# GPIO_EXPANDER_LED.net
KiCad netlist of a schematic drawn in Altium Designer
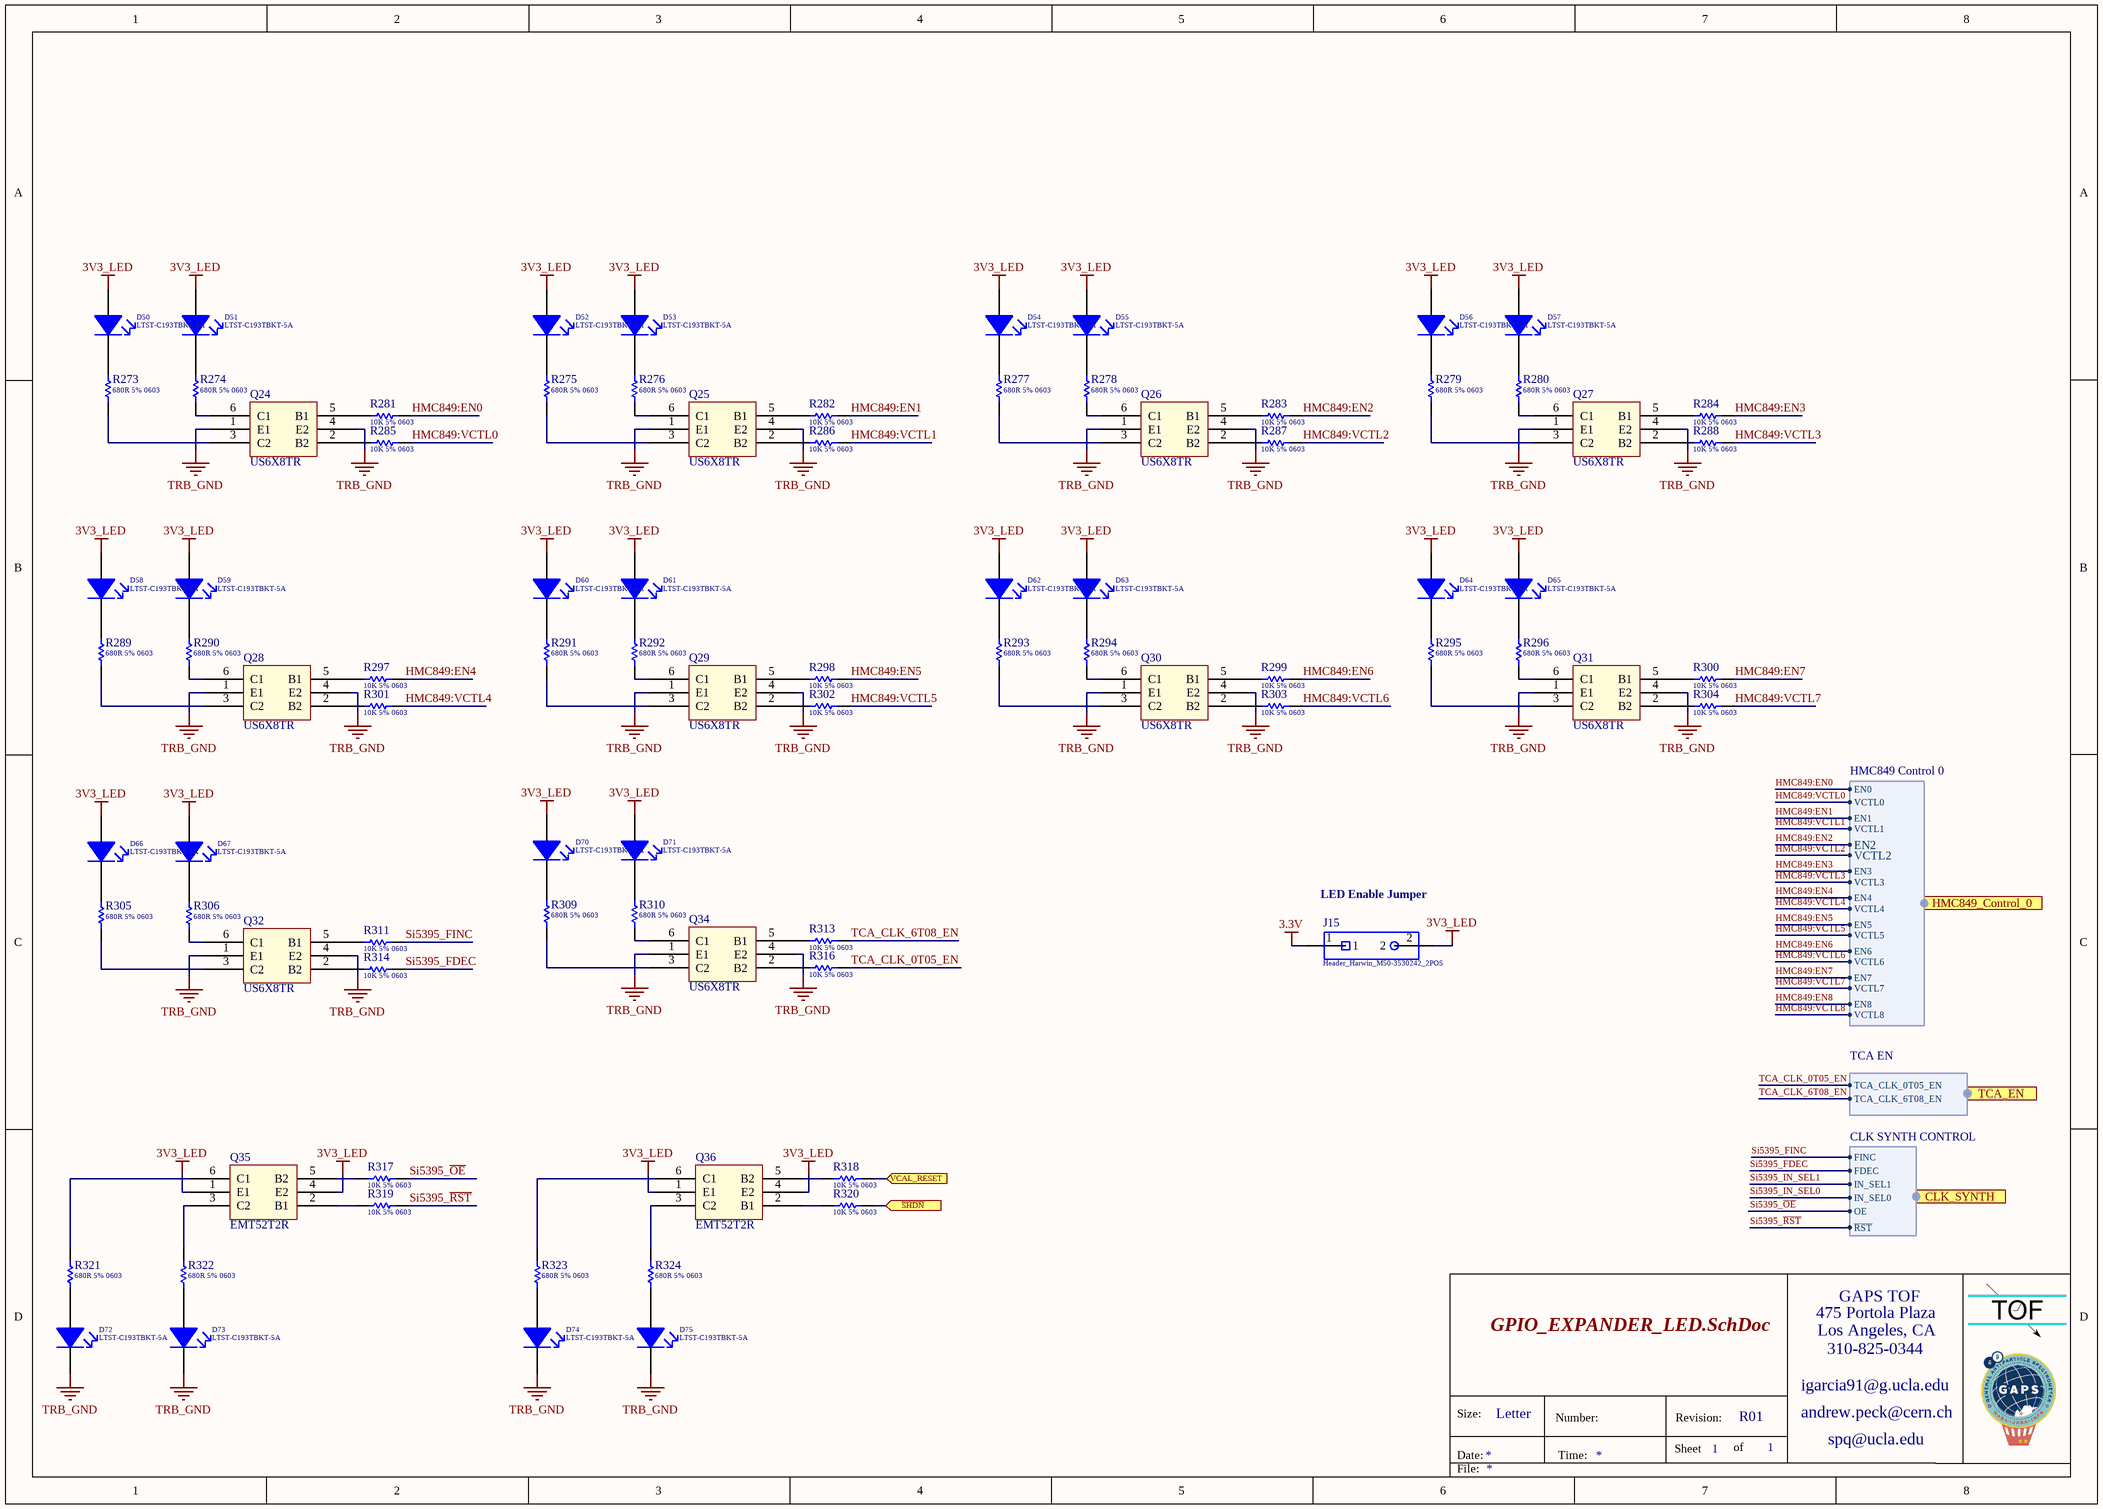
[diagram p0: GPIO_EXPANDER_LED.SchDoc]

(export (version "E")
  (design (tool "Eeschema 10.0.6"))
  (components
    (comp (ref "D50")
      (value "Led_Lite-On_LTST-C193TBKT-5A_Blue")
      (footprint "Led_Lite-On_LTST-C193TBKT-5A_Blue")
      (description "Standard LEDs - SMD Blue 470nm 28mcd 20mA")
      (fields (field (name "SERIES") "LTST-C193TBKT-5A"))
      (libsource (lib "Led_Lite-On_LTST-C193TBKT-5A_Blue") (part "Led_Lite-On_LTST-C193TBKT-5A_Blue"))
    )
    (comp (ref "D51")
      (value "Led_Lite-On_LTST-C193TBKT-5A_Blue")
      (footprint "Led_Lite-On_LTST-C193TBKT-5A_Blue")
      (description "Standard LEDs - SMD Blue 470nm 28mcd 20mA")
      (fields (field (name "SERIES") "LTST-C193TBKT-5A"))
      (libsource (lib "Led_Lite-On_LTST-C193TBKT-5A_Blue") (part "Led_Lite-On_LTST-C193TBKT-5A_Blue"))
    )
    (comp (ref "D52")
      (value "Led_Lite-On_LTST-C193TBKT-5A_Blue")
      (footprint "Led_Lite-On_LTST-C193TBKT-5A_Blue")
      (description "Standard LEDs - SMD Blue 470nm 28mcd 20mA")
      (fields (field (name "SERIES") "LTST-C193TBKT-5A"))
      (libsource (lib "Led_Lite-On_LTST-C193TBKT-5A_Blue") (part "Led_Lite-On_LTST-C193TBKT-5A_Blue"))
    )
    (comp (ref "D53")
      (value "Led_Lite-On_LTST-C193TBKT-5A_Blue")
      (footprint "Led_Lite-On_LTST-C193TBKT-5A_Blue")
      (description "Standard LEDs - SMD Blue 470nm 28mcd 20mA")
      (fields (field (name "SERIES") "LTST-C193TBKT-5A"))
      (libsource (lib "Led_Lite-On_LTST-C193TBKT-5A_Blue") (part "Led_Lite-On_LTST-C193TBKT-5A_Blue"))
    )
    (comp (ref "D54")
      (value "Led_Lite-On_LTST-C193TBKT-5A_Blue")
      (footprint "Led_Lite-On_LTST-C193TBKT-5A_Blue")
      (description "Standard LEDs - SMD Blue 470nm 28mcd 20mA")
      (fields (field (name "SERIES") "LTST-C193TBKT-5A"))
      (libsource (lib "Led_Lite-On_LTST-C193TBKT-5A_Blue") (part "Led_Lite-On_LTST-C193TBKT-5A_Blue"))
    )
    (comp (ref "D55")
      (value "Led_Lite-On_LTST-C193TBKT-5A_Blue")
      (footprint "Led_Lite-On_LTST-C193TBKT-5A_Blue")
      (description "Standard LEDs - SMD Blue 470nm 28mcd 20mA")
      (fields (field (name "SERIES") "LTST-C193TBKT-5A"))
      (libsource (lib "Led_Lite-On_LTST-C193TBKT-5A_Blue") (part "Led_Lite-On_LTST-C193TBKT-5A_Blue"))
    )
    (comp (ref "D56")
      (value "Led_Lite-On_LTST-C193TBKT-5A_Blue")
      (footprint "Led_Lite-On_LTST-C193TBKT-5A_Blue")
      (description "Standard LEDs - SMD Blue 470nm 28mcd 20mA")
      (fields (field (name "SERIES") "LTST-C193TBKT-5A"))
      (libsource (lib "Led_Lite-On_LTST-C193TBKT-5A_Blue") (part "Led_Lite-On_LTST-C193TBKT-5A_Blue"))
    )
    (comp (ref "D57")
      (value "Led_Lite-On_LTST-C193TBKT-5A_Blue")
      (footprint "Led_Lite-On_LTST-C193TBKT-5A_Blue")
      (description "Standard LEDs - SMD Blue 470nm 28mcd 20mA")
      (fields (field (name "SERIES") "LTST-C193TBKT-5A"))
      (libsource (lib "Led_Lite-On_LTST-C193TBKT-5A_Blue") (part "Led_Lite-On_LTST-C193TBKT-5A_Blue"))
    )
    (comp (ref "D58")
      (value "Led_Lite-On_LTST-C193TBKT-5A_Blue")
      (footprint "Led_Lite-On_LTST-C193TBKT-5A_Blue")
      (description "Standard LEDs - SMD Blue 470nm 28mcd 20mA")
      (fields (field (name "SERIES") "LTST-C193TBKT-5A"))
      (libsource (lib "Led_Lite-On_LTST-C193TBKT-5A_Blue") (part "Led_Lite-On_LTST-C193TBKT-5A_Blue"))
    )
    (comp (ref "D59")
      (value "Led_Lite-On_LTST-C193TBKT-5A_Blue")
      (footprint "Led_Lite-On_LTST-C193TBKT-5A_Blue")
      (description "Standard LEDs - SMD Blue 470nm 28mcd 20mA")
      (fields (field (name "SERIES") "LTST-C193TBKT-5A"))
      (libsource (lib "Led_Lite-On_LTST-C193TBKT-5A_Blue") (part "Led_Lite-On_LTST-C193TBKT-5A_Blue"))
    )
    (comp (ref "D60")
      (value "Led_Lite-On_LTST-C193TBKT-5A_Blue")
      (footprint "Led_Lite-On_LTST-C193TBKT-5A_Blue")
      (description "Standard LEDs - SMD Blue 470nm 28mcd 20mA")
      (fields (field (name "SERIES") "LTST-C193TBKT-5A"))
      (libsource (lib "Led_Lite-On_LTST-C193TBKT-5A_Blue") (part "Led_Lite-On_LTST-C193TBKT-5A_Blue"))
    )
    (comp (ref "D61")
      (value "Led_Lite-On_LTST-C193TBKT-5A_Blue")
      (footprint "Led_Lite-On_LTST-C193TBKT-5A_Blue")
      (description "Standard LEDs - SMD Blue 470nm 28mcd 20mA")
      (fields (field (name "SERIES") "LTST-C193TBKT-5A"))
      (libsource (lib "Led_Lite-On_LTST-C193TBKT-5A_Blue") (part "Led_Lite-On_LTST-C193TBKT-5A_Blue"))
    )
    (comp (ref "D62")
      (value "Led_Lite-On_LTST-C193TBKT-5A_Blue")
      (footprint "Led_Lite-On_LTST-C193TBKT-5A_Blue")
      (description "Standard LEDs - SMD Blue 470nm 28mcd 20mA")
      (fields (field (name "SERIES") "LTST-C193TBKT-5A"))
      (libsource (lib "Led_Lite-On_LTST-C193TBKT-5A_Blue") (part "Led_Lite-On_LTST-C193TBKT-5A_Blue"))
    )
    (comp (ref "D63")
      (value "Led_Lite-On_LTST-C193TBKT-5A_Blue")
      (footprint "Led_Lite-On_LTST-C193TBKT-5A_Blue")
      (description "Standard LEDs - SMD Blue 470nm 28mcd 20mA")
      (fields (field (name "SERIES") "LTST-C193TBKT-5A"))
      (libsource (lib "Led_Lite-On_LTST-C193TBKT-5A_Blue") (part "Led_Lite-On_LTST-C193TBKT-5A_Blue"))
    )
    (comp (ref "D64")
      (value "Led_Lite-On_LTST-C193TBKT-5A_Blue")
      (footprint "Led_Lite-On_LTST-C193TBKT-5A_Blue")
      (description "Standard LEDs - SMD Blue 470nm 28mcd 20mA")
      (fields (field (name "SERIES") "LTST-C193TBKT-5A"))
      (libsource (lib "Led_Lite-On_LTST-C193TBKT-5A_Blue") (part "Led_Lite-On_LTST-C193TBKT-5A_Blue"))
    )
    (comp (ref "D65")
      (value "Led_Lite-On_LTST-C193TBKT-5A_Blue")
      (footprint "Led_Lite-On_LTST-C193TBKT-5A_Blue")
      (description "Standard LEDs - SMD Blue 470nm 28mcd 20mA")
      (fields (field (name "SERIES") "LTST-C193TBKT-5A"))
      (libsource (lib "Led_Lite-On_LTST-C193TBKT-5A_Blue") (part "Led_Lite-On_LTST-C193TBKT-5A_Blue"))
    )
    (comp (ref "D66")
      (value "Led_Lite-On_LTST-C193TBKT-5A_Blue")
      (footprint "Led_Lite-On_LTST-C193TBKT-5A_Blue")
      (description "Standard LEDs - SMD Blue 470nm 28mcd 20mA")
      (fields (field (name "SERIES") "LTST-C193TBKT-5A"))
      (libsource (lib "Led_Lite-On_LTST-C193TBKT-5A_Blue") (part "Led_Lite-On_LTST-C193TBKT-5A_Blue"))
    )
    (comp (ref "D67")
      (value "Led_Lite-On_LTST-C193TBKT-5A_Blue")
      (footprint "Led_Lite-On_LTST-C193TBKT-5A_Blue")
      (description "Standard LEDs - SMD Blue 470nm 28mcd 20mA")
      (fields (field (name "SERIES") "LTST-C193TBKT-5A"))
      (libsource (lib "Led_Lite-On_LTST-C193TBKT-5A_Blue") (part "Led_Lite-On_LTST-C193TBKT-5A_Blue"))
    )
    (comp (ref "D70")
      (value "Led_Lite-On_LTST-C193TBKT-5A_Blue")
      (footprint "Led_Lite-On_LTST-C193TBKT-5A_Blue")
      (description "Standard LEDs - SMD Blue 470nm 28mcd 20mA")
      (fields (field (name "SERIES") "LTST-C193TBKT-5A"))
      (libsource (lib "Led_Lite-On_LTST-C193TBKT-5A_Blue") (part "Led_Lite-On_LTST-C193TBKT-5A_Blue"))
    )
    (comp (ref "D71")
      (value "Led_Lite-On_LTST-C193TBKT-5A_Blue")
      (footprint "Led_Lite-On_LTST-C193TBKT-5A_Blue")
      (description "Standard LEDs - SMD Blue 470nm 28mcd 20mA")
      (fields (field (name "SERIES") "LTST-C193TBKT-5A"))
      (libsource (lib "Led_Lite-On_LTST-C193TBKT-5A_Blue") (part "Led_Lite-On_LTST-C193TBKT-5A_Blue"))
    )
    (comp (ref "D72")
      (value "Led_Lite-On_LTST-C193TBKT-5A_Blue")
      (footprint "Led_Lite-On_LTST-C193TBKT-5A_Blue")
      (description "Standard LEDs - SMD Blue 470nm 28mcd 20mA")
      (fields (field (name "SERIES") "LTST-C193TBKT-5A"))
      (libsource (lib "Led_Lite-On_LTST-C193TBKT-5A_Blue") (part "Led_Lite-On_LTST-C193TBKT-5A_Blue"))
    )
    (comp (ref "D73")
      (value "Led_Lite-On_LTST-C193TBKT-5A_Blue")
      (footprint "Led_Lite-On_LTST-C193TBKT-5A_Blue")
      (description "Standard LEDs - SMD Blue 470nm 28mcd 20mA")
      (fields (field (name "SERIES") "LTST-C193TBKT-5A"))
      (libsource (lib "Led_Lite-On_LTST-C193TBKT-5A_Blue") (part "Led_Lite-On_LTST-C193TBKT-5A_Blue"))
    )
    (comp (ref "D74")
      (value "Led_Lite-On_LTST-C193TBKT-5A_Blue")
      (footprint "Led_Lite-On_LTST-C193TBKT-5A_Blue")
      (description "Standard LEDs - SMD Blue 470nm 28mcd 20mA")
      (fields (field (name "SERIES") "LTST-C193TBKT-5A"))
      (libsource (lib "Led_Lite-On_LTST-C193TBKT-5A_Blue") (part "Led_Lite-On_LTST-C193TBKT-5A_Blue"))
    )
    (comp (ref "D75")
      (value "Led_Lite-On_LTST-C193TBKT-5A_Blue")
      (footprint "Led_Lite-On_LTST-C193TBKT-5A_Blue")
      (description "Standard LEDs - SMD Blue 470nm 28mcd 20mA")
      (fields (field (name "SERIES") "LTST-C193TBKT-5A"))
      (libsource (lib "Led_Lite-On_LTST-C193TBKT-5A_Blue") (part "Led_Lite-On_LTST-C193TBKT-5A_Blue"))
    )
    (comp (ref "J15")
      (value "Header_Harwin_M50-3530242_2POS")
      (footprint "Header_Harwin_M50-3530242_2POS")
      (description "Headers & Wire Housings 2 WAY SIL VERT PC TAIL P/HDR")
      (libsource (lib "Header_Harwin_M50-3530242_2POS") (part "Header_Harwin_M50-3530242_2POS"))
    )
    (comp (ref "Q24")
      (value "BJT_ROHM_US6X8TR_1A_NPN")
      (footprint "BJT_ROHM_US6X8TR_1A_NPN")
      (description "Bipolar Transistors - BJT NPN+NPN 30VCEO 1A SOT-363T")
      (fields (field (name "SERIES") "US6X8TR"))
      (libsource (lib "BJT_ROHM_US6X8TR_1A_NPN") (part "BJT_ROHM_US6X8TR_1A_NPN"))
    )
    (comp (ref "Q25")
      (value "BJT_ROHM_US6X8TR_1A_NPN")
      (footprint "BJT_ROHM_US6X8TR_1A_NPN")
      (description "Bipolar Transistors - BJT NPN+NPN 30VCEO 1A SOT-363T")
      (fields (field (name "SERIES") "US6X8TR"))
      (libsource (lib "BJT_ROHM_US6X8TR_1A_NPN") (part "BJT_ROHM_US6X8TR_1A_NPN"))
    )
    (comp (ref "Q26")
      (value "BJT_ROHM_US6X8TR_1A_NPN")
      (footprint "BJT_ROHM_US6X8TR_1A_NPN")
      (description "Bipolar Transistors - BJT NPN+NPN 30VCEO 1A SOT-363T")
      (fields (field (name "SERIES") "US6X8TR"))
      (libsource (lib "BJT_ROHM_US6X8TR_1A_NPN") (part "BJT_ROHM_US6X8TR_1A_NPN"))
    )
    (comp (ref "Q27")
      (value "BJT_ROHM_US6X8TR_1A_NPN")
      (footprint "BJT_ROHM_US6X8TR_1A_NPN")
      (description "Bipolar Transistors - BJT NPN+NPN 30VCEO 1A SOT-363T")
      (fields (field (name "SERIES") "US6X8TR"))
      (libsource (lib "BJT_ROHM_US6X8TR_1A_NPN") (part "BJT_ROHM_US6X8TR_1A_NPN"))
    )
    (comp (ref "Q28")
      (value "BJT_ROHM_US6X8TR_1A_NPN")
      (footprint "BJT_ROHM_US6X8TR_1A_NPN")
      (description "Bipolar Transistors - BJT NPN+NPN 30VCEO 1A SOT-363T")
      (fields (field (name "SERIES") "US6X8TR"))
      (libsource (lib "BJT_ROHM_US6X8TR_1A_NPN") (part "BJT_ROHM_US6X8TR_1A_NPN"))
    )
    (comp (ref "Q29")
      (value "BJT_ROHM_US6X8TR_1A_NPN")
      (footprint "BJT_ROHM_US6X8TR_1A_NPN")
      (description "Bipolar Transistors - BJT NPN+NPN 30VCEO 1A SOT-363T")
      (fields (field (name "SERIES") "US6X8TR"))
      (libsource (lib "BJT_ROHM_US6X8TR_1A_NPN") (part "BJT_ROHM_US6X8TR_1A_NPN"))
    )
    (comp (ref "Q30")
      (value "BJT_ROHM_US6X8TR_1A_NPN")
      (footprint "BJT_ROHM_US6X8TR_1A_NPN")
      (description "Bipolar Transistors - BJT NPN+NPN 30VCEO 1A SOT-363T")
      (fields (field (name "SERIES") "US6X8TR"))
      (libsource (lib "BJT_ROHM_US6X8TR_1A_NPN") (part "BJT_ROHM_US6X8TR_1A_NPN"))
    )
    (comp (ref "Q31")
      (value "BJT_ROHM_US6X8TR_1A_NPN")
      (footprint "BJT_ROHM_US6X8TR_1A_NPN")
      (description "Bipolar Transistors - BJT NPN+NPN 30VCEO 1A SOT-363T")
      (fields (field (name "SERIES") "US6X8TR"))
      (libsource (lib "BJT_ROHM_US6X8TR_1A_NPN") (part "BJT_ROHM_US6X8TR_1A_NPN"))
    )
    (comp (ref "Q32")
      (value "BJT_ROHM_US6X8TR_1A_NPN")
      (footprint "BJT_ROHM_US6X8TR_1A_NPN")
      (description "Bipolar Transistors - BJT NPN+NPN 30VCEO 1A SOT-363T")
      (fields (field (name "SERIES") "US6X8TR"))
      (libsource (lib "BJT_ROHM_US6X8TR_1A_NPN") (part "BJT_ROHM_US6X8TR_1A_NPN"))
    )
    (comp (ref "Q34")
      (value "BJT_ROHM_US6X8TR_1A_NPN")
      (footprint "BJT_ROHM_US6X8TR_1A_NPN")
      (description "Bipolar Transistors - BJT NPN+NPN 30VCEO 1A SOT-363T")
      (fields (field (name "SERIES") "US6X8TR"))
      (libsource (lib "BJT_ROHM_US6X8TR_1A_NPN") (part "BJT_ROHM_US6X8TR_1A_NPN"))
    )
    (comp (ref "Q35")
      (value "BJT_ROHM_EMT52T2R_100mA_PNP")
      (footprint "BJT_ROHM_EMT52T2R_100mA_PNP")
      (description "Bipolar Transistors - BJT Bipolar Transistor SOT-563 SC-107C EMT6")
      (fields (field (name "SERIES") "EMT52T2R"))
      (libsource (lib "BJT_ROHM_EMT52T2R_100mA_PNP") (part "BJT_ROHM_EMT52T2R_100mA_PNP"))
    )
    (comp (ref "Q36")
      (value "BJT_ROHM_EMT52T2R_100mA_PNP")
      (footprint "BJT_ROHM_EMT52T2R_100mA_PNP")
      (description "Bipolar Transistors - BJT Bipolar Transistor SOT-563 SC-107C EMT6")
      (fields (field (name "SERIES") "EMT52T2R"))
      (libsource (lib "BJT_ROHM_EMT52T2R_100mA_PNP") (part "BJT_ROHM_EMT52T2R_100mA_PNP"))
    )
    (comp (ref "R273")
      (value "680R 5% 0603")
      (footprint "RESC0603(1608)_L")
      (description "680R 0.1W 5% 0603 (1608 Metric)  SMD")
      (fields (field (name "TOLERANCE") "5 %") (field (name "POWER") "0.1 W"))
      (libsource (lib "Altium Content Vault") (part "RES"))
    )
    (comp (ref "R274")
      (value "680R 5% 0603")
      (footprint "RESC0603(1608)_L")
      (description "680R 0.1W 5% 0603 (1608 Metric)  SMD")
      (fields (field (name "TOLERANCE") "5 %") (field (name "POWER") "0.1 W"))
      (libsource (lib "Altium Content Vault") (part "RES"))
    )
    (comp (ref "R275")
      (value "680R 5% 0603")
      (footprint "RESC0603(1608)_L")
      (description "680R 0.1W 5% 0603 (1608 Metric)  SMD")
      (fields (field (name "TOLERANCE") "5 %") (field (name "POWER") "0.1 W"))
      (libsource (lib "Altium Content Vault") (part "RES"))
    )
    (comp (ref "R276")
      (value "680R 5% 0603")
      (footprint "RESC0603(1608)_L")
      (description "680R 0.1W 5% 0603 (1608 Metric)  SMD")
      (fields (field (name "TOLERANCE") "5 %") (field (name "POWER") "0.1 W"))
      (libsource (lib "Altium Content Vault") (part "RES"))
    )
    (comp (ref "R277")
      (value "680R 5% 0603")
      (footprint "RESC0603(1608)_L")
      (description "680R 0.1W 5% 0603 (1608 Metric)  SMD")
      (fields (field (name "TOLERANCE") "5 %") (field (name "POWER") "0.1 W"))
      (libsource (lib "Altium Content Vault") (part "RES"))
    )
    (comp (ref "R278")
      (value "680R 5% 0603")
      (footprint "RESC0603(1608)_L")
      (description "680R 0.1W 5% 0603 (1608 Metric)  SMD")
      (fields (field (name "TOLERANCE") "5 %") (field (name "POWER") "0.1 W"))
      (libsource (lib "Altium Content Vault") (part "RES"))
    )
    (comp (ref "R279")
      (value "680R 5% 0603")
      (footprint "RESC0603(1608)_L")
      (description "680R 0.1W 5% 0603 (1608 Metric)  SMD")
      (fields (field (name "TOLERANCE") "5 %") (field (name "POWER") "0.1 W"))
      (libsource (lib "Altium Content Vault") (part "RES"))
    )
    (comp (ref "R280")
      (value "680R 5% 0603")
      (footprint "RESC0603(1608)_L")
      (description "680R 0.1W 5% 0603 (1608 Metric)  SMD")
      (fields (field (name "TOLERANCE") "5 %") (field (name "POWER") "0.1 W"))
      (libsource (lib "Altium Content Vault") (part "RES"))
    )
    (comp (ref "R281")
      (value "10K 5% 0603")
      (footprint "RESC0603(1608)_L")
      (description "10K 0.1W 5% 0603 (1608 Metric)  SMD")
      (fields (field (name "TOLERANCE") "5 %") (field (name "POWER") "0.1 W"))
      (libsource (lib "Altium Content Vault") (part "RES"))
    )
    (comp (ref "R282")
      (value "10K 5% 0603")
      (footprint "RESC0603(1608)_L")
      (description "10K 0.1W 5% 0603 (1608 Metric)  SMD")
      (fields (field (name "TOLERANCE") "5 %") (field (name "POWER") "0.1 W"))
      (libsource (lib "Altium Content Vault") (part "RES"))
    )
    (comp (ref "R283")
      (value "10K 5% 0603")
      (footprint "RESC0603(1608)_L")
      (description "10K 0.1W 5% 0603 (1608 Metric)  SMD")
      (fields (field (name "TOLERANCE") "5 %") (field (name "POWER") "0.1 W"))
      (libsource (lib "Altium Content Vault") (part "RES"))
    )
    (comp (ref "R284")
      (value "10K 5% 0603")
      (footprint "RESC0603(1608)_L")
      (description "10K 0.1W 5% 0603 (1608 Metric)  SMD")
      (fields (field (name "TOLERANCE") "5 %") (field (name "POWER") "0.1 W"))
      (libsource (lib "Altium Content Vault") (part "RES"))
    )
    (comp (ref "R285")
      (value "10K 5% 0603")
      (footprint "RESC0603(1608)_L")
      (description "10K 0.1W 5% 0603 (1608 Metric)  SMD")
      (fields (field (name "TOLERANCE") "5 %") (field (name "POWER") "0.1 W"))
      (libsource (lib "Altium Content Vault") (part "RES"))
    )
    (comp (ref "R286")
      (value "10K 5% 0603")
      (footprint "RESC0603(1608)_L")
      (description "10K 0.1W 5% 0603 (1608 Metric)  SMD")
      (fields (field (name "TOLERANCE") "5 %") (field (name "POWER") "0.1 W"))
      (libsource (lib "Altium Content Vault") (part "RES"))
    )
    (comp (ref "R287")
      (value "10K 5% 0603")
      (footprint "RESC0603(1608)_L")
      (description "10K 0.1W 5% 0603 (1608 Metric)  SMD")
      (fields (field (name "TOLERANCE") "5 %") (field (name "POWER") "0.1 W"))
      (libsource (lib "Altium Content Vault") (part "RES"))
    )
    (comp (ref "R288")
      (value "10K 5% 0603")
      (footprint "RESC0603(1608)_L")
      (description "10K 0.1W 5% 0603 (1608 Metric)  SMD")
      (fields (field (name "TOLERANCE") "5 %") (field (name "POWER") "0.1 W"))
      (libsource (lib "Altium Content Vault") (part "RES"))
    )
    (comp (ref "R289")
      (value "680R 5% 0603")
      (footprint "RESC0603(1608)_L")
      (description "680R 0.1W 5% 0603 (1608 Metric)  SMD")
      (fields (field (name "TOLERANCE") "5 %") (field (name "POWER") "0.1 W"))
      (libsource (lib "Altium Content Vault") (part "RES"))
    )
    (comp (ref "R290")
      (value "680R 5% 0603")
      (footprint "RESC0603(1608)_L")
      (description "680R 0.1W 5% 0603 (1608 Metric)  SMD")
      (fields (field (name "TOLERANCE") "5 %") (field (name "POWER") "0.1 W"))
      (libsource (lib "Altium Content Vault") (part "RES"))
    )
    (comp (ref "R291")
      (value "680R 5% 0603")
      (footprint "RESC0603(1608)_L")
      (description "680R 0.1W 5% 0603 (1608 Metric)  SMD")
      (fields (field (name "TOLERANCE") "5 %") (field (name "POWER") "0.1 W"))
      (libsource (lib "Altium Content Vault") (part "RES"))
    )
    (comp (ref "R292")
      (value "680R 5% 0603")
      (footprint "RESC0603(1608)_L")
      (description "680R 0.1W 5% 0603 (1608 Metric)  SMD")
      (fields (field (name "TOLERANCE") "5 %") (field (name "POWER") "0.1 W"))
      (libsource (lib "Altium Content Vault") (part "RES"))
    )
    (comp (ref "R293")
      (value "680R 5% 0603")
      (footprint "RESC0603(1608)_L")
      (description "680R 0.1W 5% 0603 (1608 Metric)  SMD")
      (fields (field (name "TOLERANCE") "5 %") (field (name "POWER") "0.1 W"))
      (libsource (lib "Altium Content Vault") (part "RES"))
    )
    (comp (ref "R294")
      (value "680R 5% 0603")
      (footprint "RESC0603(1608)_L")
      (description "680R 0.1W 5% 0603 (1608 Metric)  SMD")
      (fields (field (name "TOLERANCE") "5 %") (field (name "POWER") "0.1 W"))
      (libsource (lib "Altium Content Vault") (part "RES"))
    )
    (comp (ref "R295")
      (value "680R 5% 0603")
      (footprint "RESC0603(1608)_L")
      (description "680R 0.1W 5% 0603 (1608 Metric)  SMD")
      (fields (field (name "TOLERANCE") "5 %") (field (name "POWER") "0.1 W"))
      (libsource (lib "Altium Content Vault") (part "RES"))
    )
    (comp (ref "R296")
      (value "680R 5% 0603")
      (footprint "RESC0603(1608)_L")
      (description "680R 0.1W 5% 0603 (1608 Metric)  SMD")
      (fields (field (name "TOLERANCE") "5 %") (field (name "POWER") "0.1 W"))
      (libsource (lib "Altium Content Vault") (part "RES"))
    )
    (comp (ref "R297")
      (value "10K 5% 0603")
      (footprint "RESC0603(1608)_L")
      (description "10K 0.1W 5% 0603 (1608 Metric)  SMD")
      (fields (field (name "TOLERANCE") "5 %") (field (name "POWER") "0.1 W"))
      (libsource (lib "Altium Content Vault") (part "RES"))
    )
    (comp (ref "R298")
      (value "10K 5% 0603")
      (footprint "RESC0603(1608)_L")
      (description "10K 0.1W 5% 0603 (1608 Metric)  SMD")
      (fields (field (name "TOLERANCE") "5 %") (field (name "POWER") "0.1 W"))
      (libsource (lib "Altium Content Vault") (part "RES"))
    )
    (comp (ref "R299")
      (value "10K 5% 0603")
      (footprint "RESC0603(1608)_L")
      (description "10K 0.1W 5% 0603 (1608 Metric)  SMD")
      (fields (field (name "TOLERANCE") "5 %") (field (name "POWER") "0.1 W"))
      (libsource (lib "Altium Content Vault") (part "RES"))
    )
    (comp (ref "R300")
      (value "10K 5% 0603")
      (footprint "RESC0603(1608)_L")
      (description "10K 0.1W 5% 0603 (1608 Metric)  SMD")
      (fields (field (name "TOLERANCE") "5 %") (field (name "POWER") "0.1 W"))
      (libsource (lib "Altium Content Vault") (part "RES"))
    )
    (comp (ref "R301")
      (value "10K 5% 0603")
      (footprint "RESC0603(1608)_L")
      (description "10K 0.1W 5% 0603 (1608 Metric)  SMD")
      (fields (field (name "TOLERANCE") "5 %") (field (name "POWER") "0.1 W"))
      (libsource (lib "Altium Content Vault") (part "RES"))
    )
    (comp (ref "R302")
      (value "10K 5% 0603")
      (footprint "RESC0603(1608)_L")
      (description "10K 0.1W 5% 0603 (1608 Metric)  SMD")
      (fields (field (name "TOLERANCE") "5 %") (field (name "POWER") "0.1 W"))
      (libsource (lib "Altium Content Vault") (part "RES"))
    )
    (comp (ref "R303")
      (value "10K 5% 0603")
      (footprint "RESC0603(1608)_L")
      (description "10K 0.1W 5% 0603 (1608 Metric)  SMD")
      (fields (field (name "TOLERANCE") "5 %") (field (name "POWER") "0.1 W"))
      (libsource (lib "Altium Content Vault") (part "RES"))
    )
    (comp (ref "R304")
      (value "10K 5% 0603")
      (footprint "RESC0603(1608)_L")
      (description "10K 0.1W 5% 0603 (1608 Metric)  SMD")
      (fields (field (name "TOLERANCE") "5 %") (field (name "POWER") "0.1 W"))
      (libsource (lib "Altium Content Vault") (part "RES"))
    )
    (comp (ref "R305")
      (value "680R 5% 0603")
      (footprint "RESC0603(1608)_L")
      (description "680R 0.1W 5% 0603 (1608 Metric)  SMD")
      (fields (field (name "TOLERANCE") "5 %") (field (name "POWER") "0.1 W"))
      (libsource (lib "Altium Content Vault") (part "RES"))
    )
    (comp (ref "R306")
      (value "680R 5% 0603")
      (footprint "RESC0603(1608)_L")
      (description "680R 0.1W 5% 0603 (1608 Metric)  SMD")
      (fields (field (name "TOLERANCE") "5 %") (field (name "POWER") "0.1 W"))
      (libsource (lib "Altium Content Vault") (part "RES"))
    )
    (comp (ref "R309")
      (value "680R 5% 0603")
      (footprint "RESC0603(1608)_L")
      (description "680R 0.1W 5% 0603 (1608 Metric)  SMD")
      (fields (field (name "TOLERANCE") "5 %") (field (name "POWER") "0.1 W"))
      (libsource (lib "Altium Content Vault") (part "RES"))
    )
    (comp (ref "R310")
      (value "680R 5% 0603")
      (footprint "RESC0603(1608)_L")
      (description "680R 0.1W 5% 0603 (1608 Metric)  SMD")
      (fields (field (name "TOLERANCE") "5 %") (field (name "POWER") "0.1 W"))
      (libsource (lib "Altium Content Vault") (part "RES"))
    )
    (comp (ref "R311")
      (value "10K 5% 0603")
      (footprint "RESC0603(1608)_L")
      (description "10K 0.1W 5% 0603 (1608 Metric)  SMD")
      (fields (field (name "TOLERANCE") "5 %") (field (name "POWER") "0.1 W"))
      (libsource (lib "Altium Content Vault") (part "RES"))
    )
    (comp (ref "R313")
      (value "10K 5% 0603")
      (footprint "RESC0603(1608)_L")
      (description "10K 0.1W 5% 0603 (1608 Metric)  SMD")
      (fields (field (name "TOLERANCE") "5 %") (field (name "POWER") "0.1 W"))
      (libsource (lib "Altium Content Vault") (part "RES"))
    )
    (comp (ref "R314")
      (value "10K 5% 0603")
      (footprint "RESC0603(1608)_L")
      (description "10K 0.1W 5% 0603 (1608 Metric)  SMD")
      (fields (field (name "TOLERANCE") "5 %") (field (name "POWER") "0.1 W"))
      (libsource (lib "Altium Content Vault") (part "RES"))
    )
    (comp (ref "R316")
      (value "10K 5% 0603")
      (footprint "RESC0603(1608)_L")
      (description "10K 0.1W 5% 0603 (1608 Metric)  SMD")
      (fields (field (name "TOLERANCE") "5 %") (field (name "POWER") "0.1 W"))
      (libsource (lib "Altium Content Vault") (part "RES"))
    )
    (comp (ref "R317")
      (value "10K 5% 0603")
      (footprint "RESC0603(1608)_L")
      (description "10K 0.1W 5% 0603 (1608 Metric)  SMD")
      (fields (field (name "TOLERANCE") "5 %") (field (name "POWER") "0.1 W"))
      (libsource (lib "Altium Content Vault") (part "RES"))
    )
    (comp (ref "R318")
      (value "10K 5% 0603")
      (footprint "RESC0603(1608)_L")
      (description "10K 0.1W 5% 0603 (1608 Metric)  SMD")
      (fields (field (name "TOLERANCE") "5 %") (field (name "POWER") "0.1 W"))
      (libsource (lib "Altium Content Vault") (part "RES"))
    )
    (comp (ref "R319")
      (value "10K 5% 0603")
      (footprint "RESC0603(1608)_L")
      (description "10K 0.1W 5% 0603 (1608 Metric)  SMD")
      (fields (field (name "TOLERANCE") "5 %") (field (name "POWER") "0.1 W"))
      (libsource (lib "Altium Content Vault") (part "RES"))
    )
    (comp (ref "R320")
      (value "10K 5% 0603")
      (footprint "RESC0603(1608)_L")
      (description "10K 0.1W 5% 0603 (1608 Metric)  SMD")
      (fields (field (name "TOLERANCE") "5 %") (field (name "POWER") "0.1 W"))
      (libsource (lib "Altium Content Vault") (part "RES"))
    )
    (comp (ref "R321")
      (value "680R 5% 0603")
      (footprint "RESC0603(1608)_L")
      (description "680R 0.1W 5% 0603 (1608 Metric)  SMD")
      (fields (field (name "TOLERANCE") "5 %") (field (name "POWER") "0.1 W"))
      (libsource (lib "Altium Content Vault") (part "RES"))
    )
    (comp (ref "R322")
      (value "680R 5% 0603")
      (footprint "RESC0603(1608)_L")
      (description "680R 0.1W 5% 0603 (1608 Metric)  SMD")
      (fields (field (name "TOLERANCE") "5 %") (field (name "POWER") "0.1 W"))
      (libsource (lib "Altium Content Vault") (part "RES"))
    )
    (comp (ref "R323")
      (value "680R 5% 0603")
      (footprint "RESC0603(1608)_L")
      (description "680R 0.1W 5% 0603 (1608 Metric)  SMD")
      (fields (field (name "TOLERANCE") "5 %") (field (name "POWER") "0.1 W"))
      (libsource (lib "Altium Content Vault") (part "RES"))
    )
    (comp (ref "R324")
      (value "680R 5% 0603")
      (footprint "RESC0603(1608)_L")
      (description "680R 0.1W 5% 0603 (1608 Metric)  SMD")
      (fields (field (name "TOLERANCE") "5 %") (field (name "POWER") "0.1 W"))
      (libsource (lib "Altium Content Vault") (part "RES"))
    )
  )
  (nets
    (net (code "9") (name "/HMC849:EN0") (class "Default")
      (node (ref "R281") (pin "2") (pinfunction "2_2") (pintype "passive"))
    )
    (net (code "10") (name "/HMC849:EN1") (class "Default")
      (node (ref "R282") (pin "2") (pinfunction "2_2") (pintype "passive"))
    )
    (net (code "11") (name "/HMC849:EN2") (class "Default")
      (node (ref "R283") (pin "2") (pinfunction "2_2") (pintype "passive"))
    )
    (net (code "12") (name "/HMC849:EN3") (class "Default")
      (node (ref "R284") (pin "2") (pinfunction "2_2") (pintype "passive"))
    )
    (net (code "13") (name "/HMC849:EN4") (class "Default")
      (node (ref "R297") (pin "2") (pinfunction "2_2") (pintype "passive"))
    )
    (net (code "14") (name "/HMC849:EN5") (class "Default")
      (node (ref "R298") (pin "2") (pinfunction "2_2") (pintype "passive"))
    )
    (net (code "15") (name "/HMC849:EN6") (class "Default")
      (node (ref "R299") (pin "2") (pinfunction "2_2") (pintype "passive"))
    )
    (net (code "16") (name "/HMC849:EN7") (class "Default")
      (node (ref "R300") (pin "2") (pinfunction "2_2") (pintype "passive"))
    )
    (net (code "18") (name "/HMC849:VCTL0") (class "Default")
      (node (ref "R285") (pin "1") (pinfunction "1_1") (pintype "passive"))
    )
    (net (code "19") (name "/HMC849:VCTL1") (class "Default")
      (node (ref "R286") (pin "1") (pinfunction "1_1") (pintype "passive"))
    )
    (net (code "20") (name "/HMC849:VCTL2") (class "Default")
      (node (ref "R287") (pin "1") (pinfunction "1_1") (pintype "passive"))
    )
    (net (code "21") (name "/HMC849:VCTL3") (class "Default")
      (node (ref "R288") (pin "1") (pinfunction "1_1") (pintype "passive"))
    )
    (net (code "22") (name "/HMC849:VCTL4") (class "Default")
      (node (ref "R301") (pin "1") (pinfunction "1_1") (pintype "passive"))
    )
    (net (code "23") (name "/HMC849:VCTL5") (class "Default")
      (node (ref "R302") (pin "1") (pinfunction "1_1") (pintype "passive"))
    )
    (net (code "24") (name "/HMC849:VCTL6") (class "Default")
      (node (ref "R303") (pin "1") (pinfunction "1_1") (pintype "passive"))
    )
    (net (code "25") (name "/HMC849:VCTL7") (class "Default")
      (node (ref "R304") (pin "1") (pinfunction "1_1") (pintype "passive"))
    )
    (net (code "27") (name "/Si5395_FDEC") (class "Default")
      (node (ref "R314") (pin "1") (pinfunction "1_1") (pintype "passive"))
    )
    (net (code "28") (name "/Si5395_FINC") (class "Default")
      (node (ref "R311") (pin "2") (pinfunction "2_2") (pintype "passive"))
    )
    (net (code "31") (name "/Si5395_~{OE}") (class "Default")
      (node (ref "R317") (pin "1") (pinfunction "1_1") (pintype "passive"))
    )
    (net (code "32") (name "/Si5395_~{RST}") (class "Default")
      (node (ref "R319") (pin "2") (pinfunction "2_2") (pintype "passive"))
    )
    (net (code "33") (name "/TCA_CLK_0T05_EN") (class "Default")
      (node (ref "R316") (pin "1") (pinfunction "1_1") (pintype "passive"))
    )
    (net (code "34") (name "/TCA_CLK_6T08_EN") (class "Default")
      (node (ref "R313") (pin "2") (pinfunction "2_2") (pintype "passive"))
    )
    (net (code "35") (name "/VCAL_RESET") (class "Default")
      (node (ref "R318") (pin "1") (pinfunction "1_1") (pintype "passive"))
    )
    (net (code "39") (name "/~{SHDN}") (class "Default")
      (node (ref "R320") (pin "2") (pinfunction "2_2") (pintype "passive"))
    )
    (net (code "40") (name "3.3V") (class "Default")
      (node (ref "J15") (pin "1") (pinfunction "1_1") (pintype "passive"))
    )
    (net (code "41") (name "3V3_LED") (class "Default")
      (node (ref "D50") (pin "2") (pinfunction "A_2") (pintype "passive"))
      (node (ref "D51") (pin "2") (pinfunction "A_2") (pintype "passive"))
      (node (ref "D52") (pin "2") (pinfunction "A_2") (pintype "passive"))
      (node (ref "D53") (pin "2") (pinfunction "A_2") (pintype "passive"))
      (node (ref "D54") (pin "2") (pinfunction "A_2") (pintype "passive"))
      (node (ref "D55") (pin "2") (pinfunction "A_2") (pintype "passive"))
      (node (ref "D56") (pin "2") (pinfunction "A_2") (pintype "passive"))
      (node (ref "D57") (pin "2") (pinfunction "A_2") (pintype "passive"))
      (node (ref "D58") (pin "2") (pinfunction "A_2") (pintype "passive"))
      (node (ref "D59") (pin "2") (pinfunction "A_2") (pintype "passive"))
      (node (ref "D60") (pin "2") (pinfunction "A_2") (pintype "passive"))
      (node (ref "D61") (pin "2") (pinfunction "A_2") (pintype "passive"))
      (node (ref "D62") (pin "2") (pinfunction "A_2") (pintype "passive"))
      (node (ref "D63") (pin "2") (pinfunction "A_2") (pintype "passive"))
      (node (ref "D64") (pin "2") (pinfunction "A_2") (pintype "passive"))
      (node (ref "D65") (pin "2") (pinfunction "A_2") (pintype "passive"))
      (node (ref "D66") (pin "2") (pinfunction "A_2") (pintype "passive"))
      (node (ref "D67") (pin "2") (pinfunction "A_2") (pintype "passive"))
      (node (ref "D70") (pin "2") (pinfunction "A_2") (pintype "passive"))
      (node (ref "D71") (pin "2") (pinfunction "A_2") (pintype "passive"))
      (node (ref "J15") (pin "2") (pinfunction "2_2") (pintype "passive"))
      (node (ref "Q35") (pin "1") (pinfunction "E1_1") (pintype "passive"))
      (node (ref "Q35") (pin "4") (pinfunction "E2_4") (pintype "passive"))
      (node (ref "Q36") (pin "1") (pinfunction "E1_1") (pintype "passive"))
      (node (ref "Q36") (pin "4") (pinfunction "E2_4") (pintype "passive"))
    )
    (net (code "42") (name "Net-(D50-K)") (class "Default")
      (node (ref "D50") (pin "1") (pinfunction "K_1") (pintype "passive"))
      (node (ref "R273") (pin "2") (pinfunction "2_2") (pintype "passive"))
    )
    (net (code "43") (name "Net-(D51-K)") (class "Default")
      (node (ref "D51") (pin "1") (pinfunction "K_1") (pintype "passive"))
      (node (ref "R274") (pin "2") (pinfunction "2_2") (pintype "passive"))
    )
    (net (code "44") (name "Net-(D52-K)") (class "Default")
      (node (ref "D52") (pin "1") (pinfunction "K_1") (pintype "passive"))
      (node (ref "R275") (pin "2") (pinfunction "2_2") (pintype "passive"))
    )
    (net (code "45") (name "Net-(D53-K)") (class "Default")
      (node (ref "D53") (pin "1") (pinfunction "K_1") (pintype "passive"))
      (node (ref "R276") (pin "2") (pinfunction "2_2") (pintype "passive"))
    )
    (net (code "46") (name "Net-(D54-K)") (class "Default")
      (node (ref "D54") (pin "1") (pinfunction "K_1") (pintype "passive"))
      (node (ref "R277") (pin "2") (pinfunction "2_2") (pintype "passive"))
    )
    (net (code "47") (name "Net-(D55-K)") (class "Default")
      (node (ref "D55") (pin "1") (pinfunction "K_1") (pintype "passive"))
      (node (ref "R278") (pin "2") (pinfunction "2_2") (pintype "passive"))
    )
    (net (code "48") (name "Net-(D56-K)") (class "Default")
      (node (ref "D56") (pin "1") (pinfunction "K_1") (pintype "passive"))
      (node (ref "R279") (pin "2") (pinfunction "2_2") (pintype "passive"))
    )
    (net (code "49") (name "Net-(D57-K)") (class "Default")
      (node (ref "D57") (pin "1") (pinfunction "K_1") (pintype "passive"))
      (node (ref "R280") (pin "2") (pinfunction "2_2") (pintype "passive"))
    )
    (net (code "50") (name "Net-(D58-K)") (class "Default")
      (node (ref "D58") (pin "1") (pinfunction "K_1") (pintype "passive"))
      (node (ref "R289") (pin "2") (pinfunction "2_2") (pintype "passive"))
    )
    (net (code "51") (name "Net-(D59-K)") (class "Default")
      (node (ref "D59") (pin "1") (pinfunction "K_1") (pintype "passive"))
      (node (ref "R290") (pin "2") (pinfunction "2_2") (pintype "passive"))
    )
    (net (code "52") (name "Net-(D60-K)") (class "Default")
      (node (ref "D60") (pin "1") (pinfunction "K_1") (pintype "passive"))
      (node (ref "R291") (pin "2") (pinfunction "2_2") (pintype "passive"))
    )
    (net (code "53") (name "Net-(D61-K)") (class "Default")
      (node (ref "D61") (pin "1") (pinfunction "K_1") (pintype "passive"))
      (node (ref "R292") (pin "2") (pinfunction "2_2") (pintype "passive"))
    )
    (net (code "54") (name "Net-(D62-K)") (class "Default")
      (node (ref "D62") (pin "1") (pinfunction "K_1") (pintype "passive"))
      (node (ref "R293") (pin "2") (pinfunction "2_2") (pintype "passive"))
    )
    (net (code "55") (name "Net-(D63-K)") (class "Default")
      (node (ref "D63") (pin "1") (pinfunction "K_1") (pintype "passive"))
      (node (ref "R294") (pin "2") (pinfunction "2_2") (pintype "passive"))
    )
    (net (code "56") (name "Net-(D64-K)") (class "Default")
      (node (ref "D64") (pin "1") (pinfunction "K_1") (pintype "passive"))
      (node (ref "R295") (pin "2") (pinfunction "2_2") (pintype "passive"))
    )
    (net (code "57") (name "Net-(D65-K)") (class "Default")
      (node (ref "D65") (pin "1") (pinfunction "K_1") (pintype "passive"))
      (node (ref "R296") (pin "2") (pinfunction "2_2") (pintype "passive"))
    )
    (net (code "58") (name "Net-(D66-K)") (class "Default")
      (node (ref "D66") (pin "1") (pinfunction "K_1") (pintype "passive"))
      (node (ref "R305") (pin "2") (pinfunction "2_2") (pintype "passive"))
    )
    (net (code "59") (name "Net-(D67-K)") (class "Default")
      (node (ref "D67") (pin "1") (pinfunction "K_1") (pintype "passive"))
      (node (ref "R306") (pin "2") (pinfunction "2_2") (pintype "passive"))
    )
    (net (code "60") (name "Net-(D70-K)") (class "Default")
      (node (ref "D70") (pin "1") (pinfunction "K_1") (pintype "passive"))
      (node (ref "R309") (pin "2") (pinfunction "2_2") (pintype "passive"))
    )
    (net (code "61") (name "Net-(D71-K)") (class "Default")
      (node (ref "D71") (pin "1") (pinfunction "K_1") (pintype "passive"))
      (node (ref "R310") (pin "2") (pinfunction "2_2") (pintype "passive"))
    )
    (net (code "62") (name "Net-(D72-A)") (class "Default")
      (node (ref "D72") (pin "2") (pinfunction "A_2") (pintype "passive"))
      (node (ref "R321") (pin "1") (pinfunction "1_1") (pintype "passive"))
    )
    (net (code "63") (name "Net-(D73-A)") (class "Default")
      (node (ref "D73") (pin "2") (pinfunction "A_2") (pintype "passive"))
      (node (ref "R322") (pin "1") (pinfunction "1_1") (pintype "passive"))
    )
    (net (code "64") (name "Net-(D74-A)") (class "Default")
      (node (ref "D74") (pin "2") (pinfunction "A_2") (pintype "passive"))
      (node (ref "R323") (pin "1") (pinfunction "1_1") (pintype "passive"))
    )
    (net (code "65") (name "Net-(D75-A)") (class "Default")
      (node (ref "D75") (pin "2") (pinfunction "A_2") (pintype "passive"))
      (node (ref "R324") (pin "1") (pinfunction "1_1") (pintype "passive"))
    )
    (net (code "66") (name "Net-(Q24-B1)") (class "Default")
      (node (ref "Q24") (pin "5") (pinfunction "B1_5") (pintype "passive"))
      (node (ref "R281") (pin "1") (pinfunction "1_1") (pintype "passive"))
    )
    (net (code "67") (name "Net-(Q24-B2)") (class "Default")
      (node (ref "Q24") (pin "2") (pinfunction "B2_2") (pintype "passive"))
      (node (ref "R285") (pin "2") (pinfunction "2_2") (pintype "passive"))
    )
    (net (code "68") (name "Net-(Q24-C1)") (class "Default")
      (node (ref "Q24") (pin "6") (pinfunction "C1_6") (pintype "passive"))
      (node (ref "R274") (pin "1") (pinfunction "1_1") (pintype "passive"))
    )
    (net (code "69") (name "Net-(Q24-C2)") (class "Default")
      (node (ref "Q24") (pin "3") (pinfunction "C2_3") (pintype "passive"))
      (node (ref "R273") (pin "1") (pinfunction "1_1") (pintype "passive"))
    )
    (net (code "70") (name "Net-(Q25-B1)") (class "Default")
      (node (ref "Q25") (pin "5") (pinfunction "B1_5") (pintype "passive"))
      (node (ref "R282") (pin "1") (pinfunction "1_1") (pintype "passive"))
    )
    (net (code "71") (name "Net-(Q25-B2)") (class "Default")
      (node (ref "Q25") (pin "2") (pinfunction "B2_2") (pintype "passive"))
      (node (ref "R286") (pin "2") (pinfunction "2_2") (pintype "passive"))
    )
    (net (code "72") (name "Net-(Q25-C1)") (class "Default")
      (node (ref "Q25") (pin "6") (pinfunction "C1_6") (pintype "passive"))
      (node (ref "R276") (pin "1") (pinfunction "1_1") (pintype "passive"))
    )
    (net (code "73") (name "Net-(Q25-C2)") (class "Default")
      (node (ref "Q25") (pin "3") (pinfunction "C2_3") (pintype "passive"))
      (node (ref "R275") (pin "1") (pinfunction "1_1") (pintype "passive"))
    )
    (net (code "74") (name "Net-(Q26-B1)") (class "Default")
      (node (ref "Q26") (pin "5") (pinfunction "B1_5") (pintype "passive"))
      (node (ref "R283") (pin "1") (pinfunction "1_1") (pintype "passive"))
    )
    (net (code "75") (name "Net-(Q26-B2)") (class "Default")
      (node (ref "Q26") (pin "2") (pinfunction "B2_2") (pintype "passive"))
      (node (ref "R287") (pin "2") (pinfunction "2_2") (pintype "passive"))
    )
    (net (code "76") (name "Net-(Q26-C1)") (class "Default")
      (node (ref "Q26") (pin "6") (pinfunction "C1_6") (pintype "passive"))
      (node (ref "R278") (pin "1") (pinfunction "1_1") (pintype "passive"))
    )
    (net (code "77") (name "Net-(Q26-C2)") (class "Default")
      (node (ref "Q26") (pin "3") (pinfunction "C2_3") (pintype "passive"))
      (node (ref "R277") (pin "1") (pinfunction "1_1") (pintype "passive"))
    )
    (net (code "78") (name "Net-(Q27-B1)") (class "Default")
      (node (ref "Q27") (pin "5") (pinfunction "B1_5") (pintype "passive"))
      (node (ref "R284") (pin "1") (pinfunction "1_1") (pintype "passive"))
    )
    (net (code "79") (name "Net-(Q27-B2)") (class "Default")
      (node (ref "Q27") (pin "2") (pinfunction "B2_2") (pintype "passive"))
      (node (ref "R288") (pin "2") (pinfunction "2_2") (pintype "passive"))
    )
    (net (code "80") (name "Net-(Q27-C1)") (class "Default")
      (node (ref "Q27") (pin "6") (pinfunction "C1_6") (pintype "passive"))
      (node (ref "R280") (pin "1") (pinfunction "1_1") (pintype "passive"))
    )
    (net (code "81") (name "Net-(Q27-C2)") (class "Default")
      (node (ref "Q27") (pin "3") (pinfunction "C2_3") (pintype "passive"))
      (node (ref "R279") (pin "1") (pinfunction "1_1") (pintype "passive"))
    )
    (net (code "82") (name "Net-(Q28-B1)") (class "Default")
      (node (ref "Q28") (pin "5") (pinfunction "B1_5") (pintype "passive"))
      (node (ref "R297") (pin "1") (pinfunction "1_1") (pintype "passive"))
    )
    (net (code "83") (name "Net-(Q28-B2)") (class "Default")
      (node (ref "Q28") (pin "2") (pinfunction "B2_2") (pintype "passive"))
      (node (ref "R301") (pin "2") (pinfunction "2_2") (pintype "passive"))
    )
    (net (code "84") (name "Net-(Q28-C1)") (class "Default")
      (node (ref "Q28") (pin "6") (pinfunction "C1_6") (pintype "passive"))
      (node (ref "R290") (pin "1") (pinfunction "1_1") (pintype "passive"))
    )
    (net (code "85") (name "Net-(Q28-C2)") (class "Default")
      (node (ref "Q28") (pin "3") (pinfunction "C2_3") (pintype "passive"))
      (node (ref "R289") (pin "1") (pinfunction "1_1") (pintype "passive"))
    )
    (net (code "86") (name "Net-(Q29-B1)") (class "Default")
      (node (ref "Q29") (pin "5") (pinfunction "B1_5") (pintype "passive"))
      (node (ref "R298") (pin "1") (pinfunction "1_1") (pintype "passive"))
    )
    (net (code "87") (name "Net-(Q29-B2)") (class "Default")
      (node (ref "Q29") (pin "2") (pinfunction "B2_2") (pintype "passive"))
      (node (ref "R302") (pin "2") (pinfunction "2_2") (pintype "passive"))
    )
    (net (code "88") (name "Net-(Q29-C1)") (class "Default")
      (node (ref "Q29") (pin "6") (pinfunction "C1_6") (pintype "passive"))
      (node (ref "R292") (pin "1") (pinfunction "1_1") (pintype "passive"))
    )
    (net (code "89") (name "Net-(Q29-C2)") (class "Default")
      (node (ref "Q29") (pin "3") (pinfunction "C2_3") (pintype "passive"))
      (node (ref "R291") (pin "1") (pinfunction "1_1") (pintype "passive"))
    )
    (net (code "90") (name "Net-(Q30-B1)") (class "Default")
      (node (ref "Q30") (pin "5") (pinfunction "B1_5") (pintype "passive"))
      (node (ref "R299") (pin "1") (pinfunction "1_1") (pintype "passive"))
    )
    (net (code "91") (name "Net-(Q30-B2)") (class "Default")
      (node (ref "Q30") (pin "2") (pinfunction "B2_2") (pintype "passive"))
      (node (ref "R303") (pin "2") (pinfunction "2_2") (pintype "passive"))
    )
    (net (code "92") (name "Net-(Q30-C1)") (class "Default")
      (node (ref "Q30") (pin "6") (pinfunction "C1_6") (pintype "passive"))
      (node (ref "R294") (pin "1") (pinfunction "1_1") (pintype "passive"))
    )
    (net (code "93") (name "Net-(Q30-C2)") (class "Default")
      (node (ref "Q30") (pin "3") (pinfunction "C2_3") (pintype "passive"))
      (node (ref "R293") (pin "1") (pinfunction "1_1") (pintype "passive"))
    )
    (net (code "94") (name "Net-(Q31-B1)") (class "Default")
      (node (ref "Q31") (pin "5") (pinfunction "B1_5") (pintype "passive"))
      (node (ref "R300") (pin "1") (pinfunction "1_1") (pintype "passive"))
    )
    (net (code "95") (name "Net-(Q31-B2)") (class "Default")
      (node (ref "Q31") (pin "2") (pinfunction "B2_2") (pintype "passive"))
      (node (ref "R304") (pin "2") (pinfunction "2_2") (pintype "passive"))
    )
    (net (code "96") (name "Net-(Q31-C1)") (class "Default")
      (node (ref "Q31") (pin "6") (pinfunction "C1_6") (pintype "passive"))
      (node (ref "R296") (pin "1") (pinfunction "1_1") (pintype "passive"))
    )
    (net (code "97") (name "Net-(Q31-C2)") (class "Default")
      (node (ref "Q31") (pin "3") (pinfunction "C2_3") (pintype "passive"))
      (node (ref "R295") (pin "1") (pinfunction "1_1") (pintype "passive"))
    )
    (net (code "98") (name "Net-(Q32-B1)") (class "Default")
      (node (ref "Q32") (pin "5") (pinfunction "B1_5") (pintype "passive"))
      (node (ref "R311") (pin "1") (pinfunction "1_1") (pintype "passive"))
    )
    (net (code "99") (name "Net-(Q32-B2)") (class "Default")
      (node (ref "Q32") (pin "2") (pinfunction "B2_2") (pintype "passive"))
      (node (ref "R314") (pin "2") (pinfunction "2_2") (pintype "passive"))
    )
    (net (code "100") (name "Net-(Q32-C1)") (class "Default")
      (node (ref "Q32") (pin "6") (pinfunction "C1_6") (pintype "passive"))
      (node (ref "R306") (pin "1") (pinfunction "1_1") (pintype "passive"))
    )
    (net (code "101") (name "Net-(Q32-C2)") (class "Default")
      (node (ref "Q32") (pin "3") (pinfunction "C2_3") (pintype "passive"))
      (node (ref "R305") (pin "1") (pinfunction "1_1") (pintype "passive"))
    )
    (net (code "102") (name "Net-(Q34-B1)") (class "Default")
      (node (ref "Q34") (pin "5") (pinfunction "B1_5") (pintype "passive"))
      (node (ref "R313") (pin "1") (pinfunction "1_1") (pintype "passive"))
    )
    (net (code "103") (name "Net-(Q34-B2)") (class "Default")
      (node (ref "Q34") (pin "2") (pinfunction "B2_2") (pintype "passive"))
      (node (ref "R316") (pin "2") (pinfunction "2_2") (pintype "passive"))
    )
    (net (code "104") (name "Net-(Q34-C1)") (class "Default")
      (node (ref "Q34") (pin "6") (pinfunction "C1_6") (pintype "passive"))
      (node (ref "R310") (pin "1") (pinfunction "1_1") (pintype "passive"))
    )
    (net (code "105") (name "Net-(Q34-C2)") (class "Default")
      (node (ref "Q34") (pin "3") (pinfunction "C2_3") (pintype "passive"))
      (node (ref "R309") (pin "1") (pinfunction "1_1") (pintype "passive"))
    )
    (net (code "106") (name "Net-(Q35-B1)") (class "Default")
      (node (ref "Q35") (pin "2") (pinfunction "B1_2") (pintype "passive"))
      (node (ref "R319") (pin "1") (pinfunction "1_1") (pintype "passive"))
    )
    (net (code "107") (name "Net-(Q35-B2)") (class "Default")
      (node (ref "Q35") (pin "5") (pinfunction "B2_5") (pintype "passive"))
      (node (ref "R317") (pin "2") (pinfunction "2_2") (pintype "passive"))
    )
    (net (code "108") (name "Net-(Q35-C1)") (class "Default")
      (node (ref "Q35") (pin "6") (pinfunction "C1_6") (pintype "passive"))
      (node (ref "R321") (pin "2") (pinfunction "2_2") (pintype "passive"))
    )
    (net (code "109") (name "Net-(Q35-C2)") (class "Default")
      (node (ref "Q35") (pin "3") (pinfunction "C2_3") (pintype "passive"))
      (node (ref "R322") (pin "2") (pinfunction "2_2") (pintype "passive"))
    )
    (net (code "110") (name "Net-(Q36-B1)") (class "Default")
      (node (ref "Q36") (pin "2") (pinfunction "B1_2") (pintype "passive"))
      (node (ref "R320") (pin "1") (pinfunction "1_1") (pintype "passive"))
    )
    (net (code "111") (name "Net-(Q36-B2)") (class "Default")
      (node (ref "Q36") (pin "5") (pinfunction "B2_5") (pintype "passive"))
      (node (ref "R318") (pin "2") (pinfunction "2_2") (pintype "passive"))
    )
    (net (code "112") (name "Net-(Q36-C1)") (class "Default")
      (node (ref "Q36") (pin "6") (pinfunction "C1_6") (pintype "passive"))
      (node (ref "R323") (pin "2") (pinfunction "2_2") (pintype "passive"))
    )
    (net (code "113") (name "Net-(Q36-C2)") (class "Default")
      (node (ref "Q36") (pin "3") (pinfunction "C2_3") (pintype "passive"))
      (node (ref "R324") (pin "2") (pinfunction "2_2") (pintype "passive"))
    )
    (net (code "114") (name "TRB_GND") (class "Default")
      (node (ref "D72") (pin "1") (pinfunction "K_1") (pintype "passive"))
      (node (ref "D73") (pin "1") (pinfunction "K_1") (pintype "passive"))
      (node (ref "D74") (pin "1") (pinfunction "K_1") (pintype "passive"))
      (node (ref "D75") (pin "1") (pinfunction "K_1") (pintype "passive"))
      (node (ref "Q24") (pin "1") (pinfunction "E1_1") (pintype "passive"))
      (node (ref "Q24") (pin "4") (pinfunction "E2_4") (pintype "passive"))
      (node (ref "Q25") (pin "1") (pinfunction "E1_1") (pintype "passive"))
      (node (ref "Q25") (pin "4") (pinfunction "E2_4") (pintype "passive"))
      (node (ref "Q26") (pin "1") (pinfunction "E1_1") (pintype "passive"))
      (node (ref "Q26") (pin "4") (pinfunction "E2_4") (pintype "passive"))
      (node (ref "Q27") (pin "1") (pinfunction "E1_1") (pintype "passive"))
      (node (ref "Q27") (pin "4") (pinfunction "E2_4") (pintype "passive"))
      (node (ref "Q28") (pin "1") (pinfunction "E1_1") (pintype "passive"))
      (node (ref "Q28") (pin "4") (pinfunction "E2_4") (pintype "passive"))
      (node (ref "Q29") (pin "1") (pinfunction "E1_1") (pintype "passive"))
      (node (ref "Q29") (pin "4") (pinfunction "E2_4") (pintype "passive"))
      (node (ref "Q30") (pin "1") (pinfunction "E1_1") (pintype "passive"))
      (node (ref "Q30") (pin "4") (pinfunction "E2_4") (pintype "passive"))
      (node (ref "Q31") (pin "1") (pinfunction "E1_1") (pintype "passive"))
      (node (ref "Q31") (pin "4") (pinfunction "E2_4") (pintype "passive"))
      (node (ref "Q32") (pin "1") (pinfunction "E1_1") (pintype "passive"))
      (node (ref "Q32") (pin "4") (pinfunction "E2_4") (pintype "passive"))
      (node (ref "Q34") (pin "1") (pinfunction "E1_1") (pintype "passive"))
      (node (ref "Q34") (pin "4") (pinfunction "E2_4") (pintype "passive"))
    )
  )
)
